# afe_revB.net
KiCad netlist of a schematic drawn in EAGLE
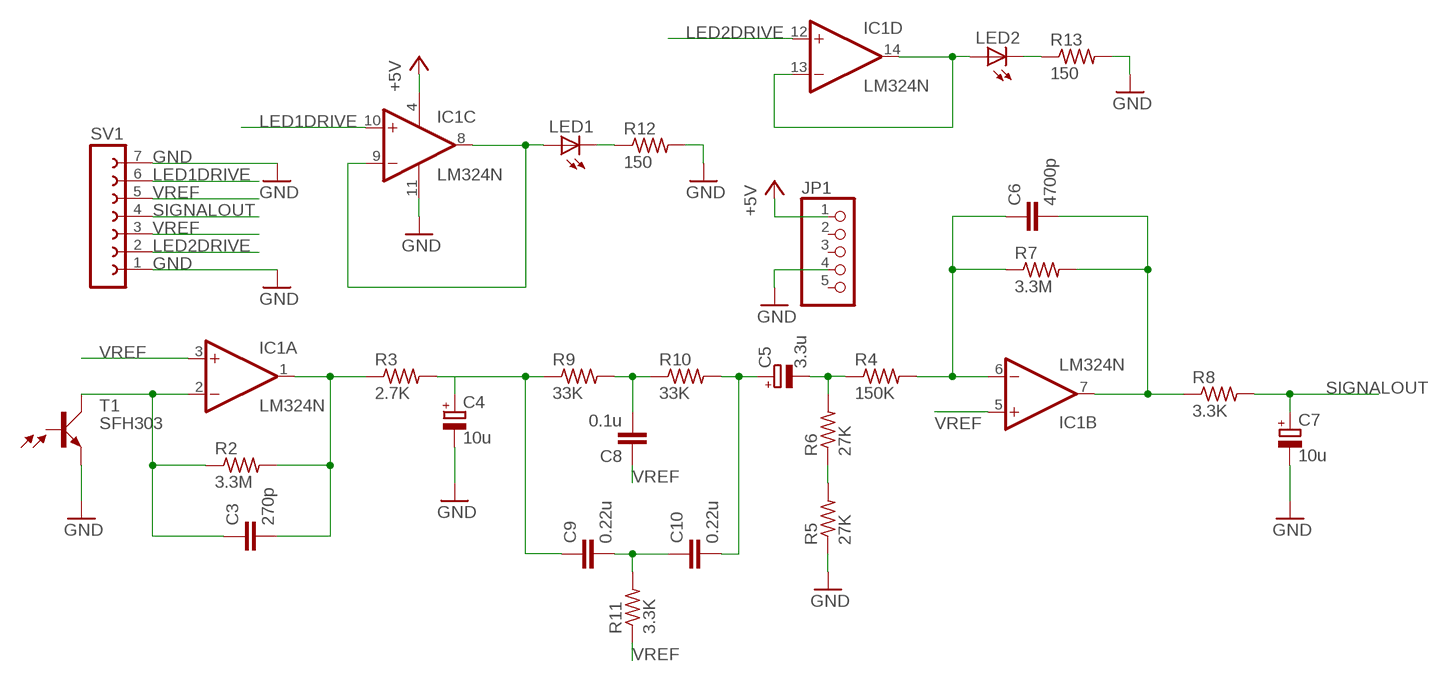
[diagram p0: schematic, sheet 1]

(export (version "E")
  (design (tool "Eeschema 10.0.6"))
  (components
    (comp (ref "C3")
      (value "270p")
      (footprint "eagle-import:C050-024X044")
      (libsource (lib "eagle-import") (part "C-EU050-024X044"))
    )
    (comp (ref "C4")
      (value "10u")
      (footprint "eagle-import:E2,5-5")
      (libsource (lib "eagle-import") (part "CPOL-EUE2.5-5"))
    )
    (comp (ref "C5")
      (value "3.3u")
      (footprint "eagle-import:E2,5-5")
      (libsource (lib "eagle-import") (part "CPOL-EUE2.5-5"))
    )
    (comp (ref "C6")
      (value "4700p")
      (footprint "eagle-import:C050-024X044")
      (libsource (lib "eagle-import") (part "C-EU050-024X044"))
    )
    (comp (ref "C7")
      (value "10u")
      (footprint "eagle-import:E2,5-5")
      (libsource (lib "eagle-import") (part "CPOL-EUE2.5-5"))
    )
    (comp (ref "C8")
      (value "0.1u")
      (footprint "eagle-import:C050-024X044")
      (libsource (lib "eagle-import") (part "C-EU050-024X044"))
    )
    (comp (ref "C9")
      (value "0.22u")
      (footprint "eagle-import:C102-043X133")
      (libsource (lib "eagle-import") (part "C-EU102-043X133"))
    )
    (comp (ref "C10")
      (value "0.22u")
      (footprint "eagle-import:C102-043X133")
      (libsource (lib "eagle-import") (part "C-EU102-043X133"))
    )
    (comp (ref "IC1")
      (value "LM324N")
      (footprint "eagle-import:DIL14")
      (libsource (lib "eagle-import") (part "LM324N"))
    )
    (comp (ref "JP1")
      (value "PINHD-1X5")
      (footprint "eagle-import:1X05")
      (libsource (lib "eagle-import") (part "PINHD-1X5"))
    )
    (comp (ref "LED1")
      (value "LED5MM")
      (footprint "eagle-import:LED5MM")
      (libsource (lib "eagle-import") (part "LED5MM"))
    )
    (comp (ref "LED2")
      (value "LED5MM")
      (footprint "eagle-import:LED5MM")
      (libsource (lib "eagle-import") (part "LED5MM"))
    )
    (comp (ref "R2")
      (value "3.3M")
      (footprint "eagle-import:0207_10")
      (libsource (lib "eagle-import") (part "R-US_0207/10"))
    )
    (comp (ref "R3")
      (value "2.7K")
      (footprint "eagle-import:0207_10")
      (libsource (lib "eagle-import") (part "R-US_0207/10"))
    )
    (comp (ref "R4")
      (value "150K")
      (footprint "eagle-import:0207_10")
      (libsource (lib "eagle-import") (part "R-US_0207/10"))
    )
    (comp (ref "R5")
      (value "27K")
      (footprint "eagle-import:0207_10")
      (libsource (lib "eagle-import") (part "R-US_0207/10"))
    )
    (comp (ref "R6")
      (value "27K")
      (footprint "eagle-import:0207_10")
      (libsource (lib "eagle-import") (part "R-US_0207/10"))
    )
    (comp (ref "R7")
      (value "3.3M")
      (footprint "eagle-import:0207_10")
      (libsource (lib "eagle-import") (part "R-US_0207/10"))
    )
    (comp (ref "R8")
      (value "3.3K")
      (footprint "eagle-import:0207_10")
      (libsource (lib "eagle-import") (part "R-US_0207/10"))
    )
    (comp (ref "R9")
      (value "33K")
      (footprint "eagle-import:0207_10")
      (libsource (lib "eagle-import") (part "R-US_0207/10"))
    )
    (comp (ref "R10")
      (value "33K")
      (footprint "eagle-import:0207_10")
      (libsource (lib "eagle-import") (part "R-US_0207/10"))
    )
    (comp (ref "R11")
      (value "3.3K")
      (footprint "eagle-import:0207_10")
      (libsource (lib "eagle-import") (part "R-US_0207/10"))
    )
    (comp (ref "R12")
      (value "150")
      (footprint "eagle-import:0207_10")
      (libsource (lib "eagle-import") (part "R-US_0207/10"))
    )
    (comp (ref "R13")
      (value "150")
      (footprint "eagle-import:0207_10")
      (libsource (lib "eagle-import") (part "R-US_0207/10"))
    )
    (comp (ref "SV1")
      (value "FE07-1")
      (footprint "eagle-import:FE07")
      (libsource (lib "eagle-import") (part "FE07-1"))
    )
    (comp (ref "T1")
      (value "SFH303")
      (footprint "eagle-import:SFH303")
      (libsource (lib "eagle-import") (part "SFH303"))
    )
  )
  (nets
    (net (code "1") (name "+5V") (class "Default")
      (node (ref "IC1") (pin "4") (pinfunction "V+_4") (pintype "power_in"))
      (node (ref "JP1") (pin "1") (pinfunction "1_1") (pintype "passive"))
    )
    (net (code "2") (name "/LED1DRIVE") (class "Default")
      (node (ref "IC1") (pin "10") (pinfunction "+IN_10") (pintype "input"))
      (node (ref "SV1") (pin "6") (pinfunction "6_6") (pintype "passive"))
    )
    (net (code "3") (name "/LED2DRIVE") (class "Default")
      (node (ref "IC1") (pin "12") (pinfunction "+IN_12") (pintype "input"))
      (node (ref "SV1") (pin "2") (pinfunction "2_2") (pintype "passive"))
    )
    (net (code "4") (name "/SIGNALOUT") (class "Default")
      (node (ref "C7") (pin "+") (pinfunction "+_+") (pintype "passive"))
      (node (ref "R8") (pin "2") (pinfunction "2_2") (pintype "passive"))
      (node (ref "SV1") (pin "4") (pinfunction "4_4") (pintype "passive"))
    )
    (net (code "5") (name "/VREF") (class "Default")
      (node (ref "C8") (pin "1") (pinfunction "1_1") (pintype "passive"))
      (node (ref "IC1") (pin "3") (pinfunction "+IN_3") (pintype "input"))
      (node (ref "IC1") (pin "5") (pinfunction "+IN_5") (pintype "input"))
      (node (ref "R11") (pin "1") (pinfunction "1_1") (pintype "passive"))
      (node (ref "SV1") (pin "3") (pinfunction "3_3") (pintype "passive"))
      (node (ref "SV1") (pin "5") (pinfunction "5_5") (pintype "passive"))
    )
    (net (code "6") (name "GND") (class "Default")
      (node (ref "C4") (pin "-") (pinfunction "-_-") (pintype "passive"))
      (node (ref "C7") (pin "-") (pinfunction "-_-") (pintype "passive"))
      (node (ref "IC1") (pin "11") (pinfunction "V-_11") (pintype "power_in"))
      (node (ref "JP1") (pin "4") (pinfunction "4_4") (pintype "passive"))
      (node (ref "R12") (pin "2") (pinfunction "2_2") (pintype "passive"))
      (node (ref "R13") (pin "2") (pinfunction "2_2") (pintype "passive"))
      (node (ref "R5") (pin "1") (pinfunction "1_1") (pintype "passive"))
      (node (ref "SV1") (pin "1") (pinfunction "1_1") (pintype "passive"))
      (node (ref "SV1") (pin "7") (pinfunction "7_7") (pintype "passive"))
      (node (ref "T1") (pin "1") (pinfunction "E_1") (pintype "passive"))
    )
    (net (code "7") (name "Net-(C4-Pad+)") (class "Default")
      (node (ref "C4") (pin "+") (pinfunction "+_+") (pintype "passive"))
      (node (ref "C9") (pin "1") (pinfunction "1_1") (pintype "passive"))
      (node (ref "R3") (pin "2") (pinfunction "2_2") (pintype "passive"))
      (node (ref "R9") (pin "1") (pinfunction "1_1") (pintype "passive"))
    )
    (net (code "8") (name "Net-(C5-Pad-)") (class "Default")
      (node (ref "C5") (pin "-") (pinfunction "-_-") (pintype "passive"))
      (node (ref "R4") (pin "1") (pinfunction "1_1") (pintype "passive"))
      (node (ref "R6") (pin "2") (pinfunction "2_2") (pintype "passive"))
    )
    (net (code "9") (name "Net-(C8-Pad2)") (class "Default")
      (node (ref "C8") (pin "2") (pinfunction "2_2") (pintype "passive"))
      (node (ref "R10") (pin "1") (pinfunction "1_1") (pintype "passive"))
      (node (ref "R9") (pin "2") (pinfunction "2_2") (pintype "passive"))
    )
    (net (code "10") (name "Net-(C10-Pad1)") (class "Default")
      (node (ref "C10") (pin "1") (pinfunction "1_1") (pintype "passive"))
      (node (ref "C9") (pin "2") (pinfunction "2_2") (pintype "passive"))
      (node (ref "R11") (pin "2") (pinfunction "2_2") (pintype "passive"))
    )
    (net (code "11") (name "Net-(C10-Pad2)") (class "Default")
      (node (ref "C10") (pin "2") (pinfunction "2_2") (pintype "passive"))
      (node (ref "C5") (pin "+") (pinfunction "+_+") (pintype "passive"))
      (node (ref "R10") (pin "2") (pinfunction "2_2") (pintype "passive"))
    )
    (net (code "12") (name "Net-(IC1A--IN)") (class "Default")
      (node (ref "C3") (pin "1") (pinfunction "1_1") (pintype "passive"))
      (node (ref "IC1") (pin "2") (pinfunction "-IN_2") (pintype "input"))
      (node (ref "R2") (pin "1") (pinfunction "1_1") (pintype "passive"))
      (node (ref "T1") (pin "2") (pinfunction "C_2") (pintype "passive"))
    )
    (net (code "13") (name "Net-(IC1A-OUT)") (class "Default")
      (node (ref "C3") (pin "2") (pinfunction "2_2") (pintype "passive"))
      (node (ref "IC1") (pin "1") (pinfunction "OUT_1") (pintype "output"))
      (node (ref "R2") (pin "2") (pinfunction "2_2") (pintype "passive"))
      (node (ref "R3") (pin "1") (pinfunction "1_1") (pintype "passive"))
    )
    (net (code "14") (name "Net-(IC1B--IN)") (class "Default")
      (node (ref "C6") (pin "1") (pinfunction "1_1") (pintype "passive"))
      (node (ref "IC1") (pin "6") (pinfunction "-IN_6") (pintype "input"))
      (node (ref "R4") (pin "2") (pinfunction "2_2") (pintype "passive"))
      (node (ref "R7") (pin "1") (pinfunction "1_1") (pintype "passive"))
    )
    (net (code "15") (name "Net-(IC1B-OUT)") (class "Default")
      (node (ref "C6") (pin "2") (pinfunction "2_2") (pintype "passive"))
      (node (ref "IC1") (pin "7") (pinfunction "OUT_7") (pintype "output"))
      (node (ref "R7") (pin "2") (pinfunction "2_2") (pintype "passive"))
      (node (ref "R8") (pin "1") (pinfunction "1_1") (pintype "passive"))
    )
    (net (code "16") (name "Net-(IC1C--IN)") (class "Default")
      (node (ref "IC1") (pin "8") (pinfunction "OUT_8") (pintype "output"))
      (node (ref "IC1") (pin "9") (pinfunction "-IN_9") (pintype "input"))
      (node (ref "LED1") (pin "A") (pinfunction "A_A") (pintype "passive"))
    )
    (net (code "17") (name "Net-(IC1D--IN)") (class "Default")
      (node (ref "IC1") (pin "13") (pinfunction "-IN_13") (pintype "input"))
      (node (ref "IC1") (pin "14") (pinfunction "OUT_14") (pintype "output"))
      (node (ref "LED2") (pin "A") (pinfunction "A_A") (pintype "passive"))
    )
    (net (code "18") (name "Net-(LED1-C)") (class "Default")
      (node (ref "LED1") (pin "K") (pinfunction "C_K") (pintype "passive"))
      (node (ref "R12") (pin "1") (pinfunction "1_1") (pintype "passive"))
    )
    (net (code "19") (name "Net-(LED2-C)") (class "Default")
      (node (ref "LED2") (pin "K") (pinfunction "C_K") (pintype "passive"))
      (node (ref "R13") (pin "1") (pinfunction "1_1") (pintype "passive"))
    )
    (net (code "20") (name "Net-(R5-Pad2)") (class "Default")
      (node (ref "R5") (pin "2") (pinfunction "2_2") (pintype "passive"))
      (node (ref "R6") (pin "1") (pinfunction "1_1") (pintype "passive"))
    )
    (net (code "21") (name "unconnected-(JP1-Pad2)") (class "Default")
      (node (ref "JP1") (pin "2") (pinfunction "2_2") (pintype "passive"))
    )
    (net (code "22") (name "unconnected-(JP1-Pad3)") (class "Default")
      (node (ref "JP1") (pin "3") (pinfunction "3_3") (pintype "passive"))
    )
    (net (code "23") (name "unconnected-(JP1-Pad5)") (class "Default")
      (node (ref "JP1") (pin "5") (pinfunction "5_5") (pintype "passive"))
    )
    (net (code "24") (name "unconnected-(T1-B-Pad3)") (class "Default")
      (node (ref "T1") (pin "3") (pinfunction "B_3") (pintype "passive"))
    )
  )
)
